# DM6010.net
KiCad netlist of a schematic drawn in Altium Designer
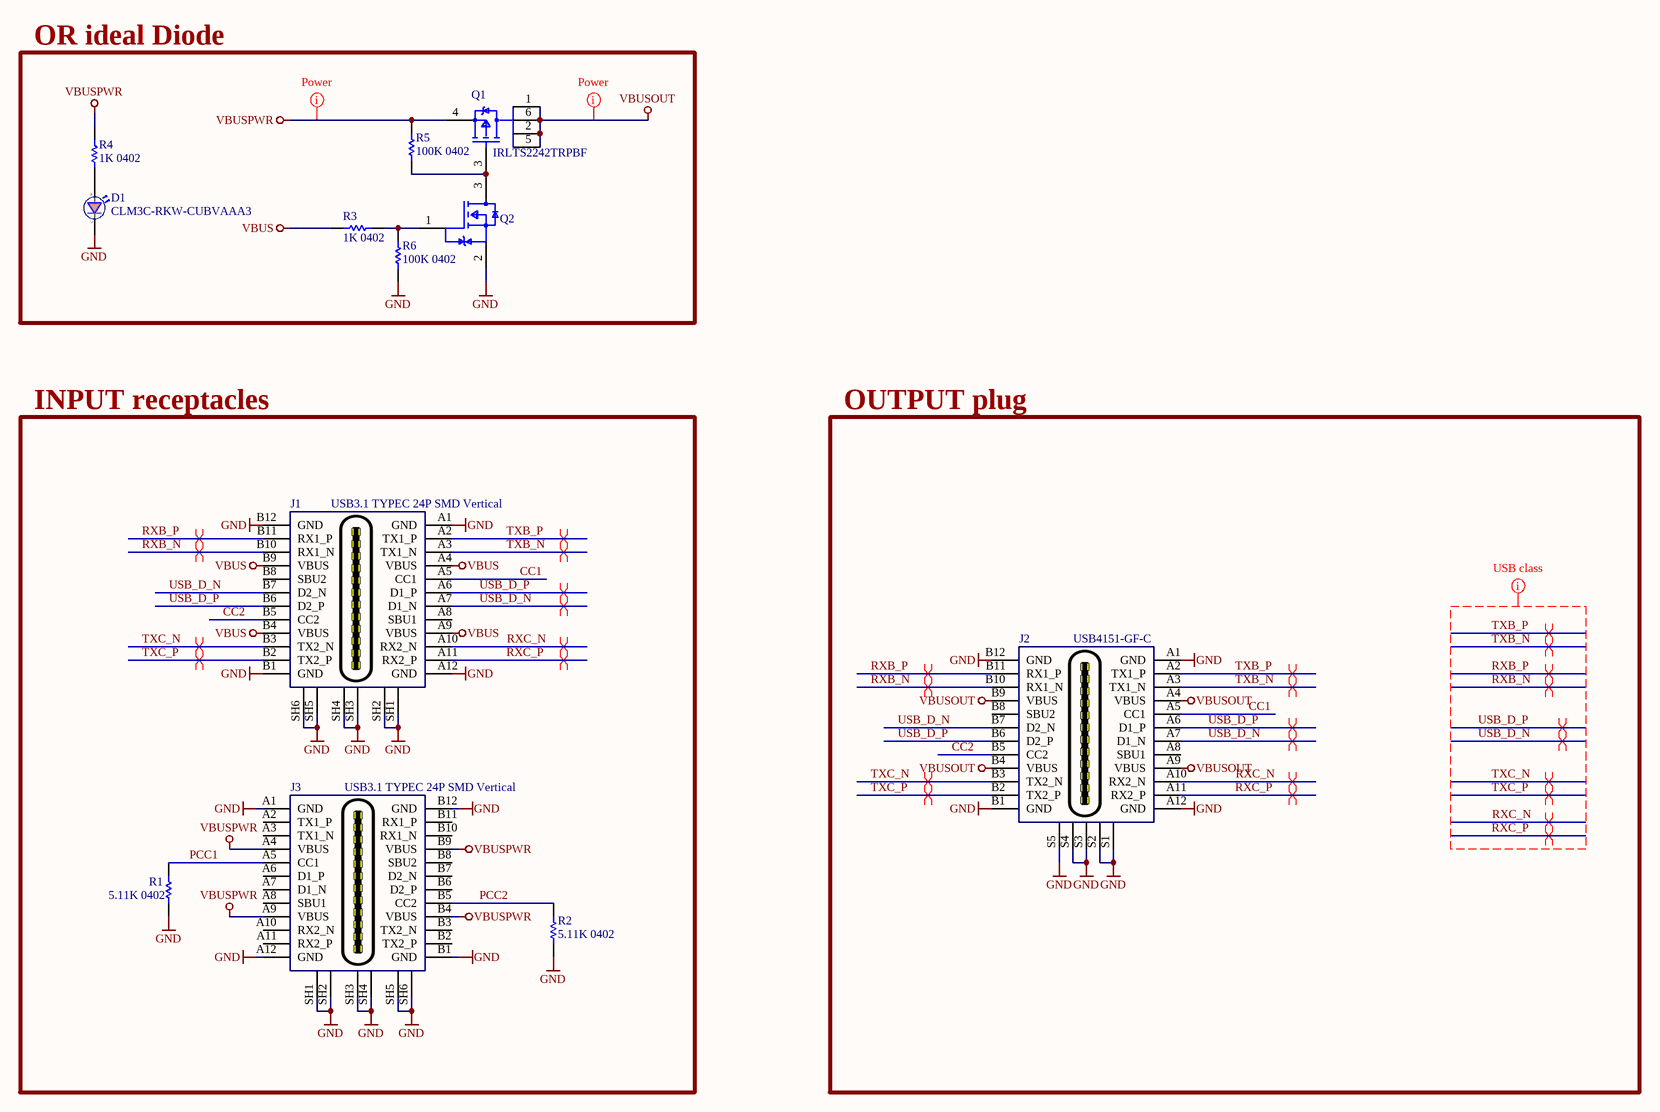
[diagram p0: DM6010.SchDoc]

(export (version "E")
  (design (tool "Eeschema 10.0.6"))
  (components
    (comp (ref "D1")
      (value "CLM3C-RKW-CUBVAAA3")
      (footprint "CLM3C-RKW-CUBVAAA3")
      (description "Single Color LED, Red")
      (libsource (lib "DM6010_R0M0E0") (part "CLM3C-RKW-CUBVAAA3"))
    )
    (comp (ref "J1")
      (value "USB3.1 TYPEC 24P SMD Vertical")
      (footprint "DM6010_R0M0E0:CX80B1-24P")
      (description "CONN RCPT USB3.1 TYPEC 24POS SMD Vertical")
      (libsource (lib "") (part "CX80B1-24P_1"))
    )
    (comp (ref "J2")
      (value "USB4151-GF-C")
      (footprint "GCT_USB4151-GF-C_REVA")
      (description "USB Connector, 24 Contact(s), Male, Straight, Surface Mount Terminal, Locking, Plug")
      (libsource (lib "DM6010_R0M0E0") (part "USB4151-GF-C"))
    )
    (comp (ref "J3")
      (value "USB3.1 TYPEC 24P SMD Vertical")
      (footprint "DM6010_R0M0E0:CX80B1-24P")
      (description "CONN RCPT USB3.1 TYPEC 24POS SMD Vertical")
      (libsource (lib "DM6010_R0M0E0") (part "CX80B1-24P"))
    )
    (comp (ref "Q1")
      (value "IRLTS2242TRPBF")
      (footprint "TSOP-6-MFG")
      (description "MOSFET P-CH 20V 6.9A 6TSOP")
      (libsource (lib "DM6010_R0M0E0") (part "IRLTS2242TRPBF"))
    )
    (comp (ref "Q2")
      (value "RE1C002UNTCL")
      (footprint "LuxonisMaster:RE1C002UNTCL")
      (description "VISHAY - SI1062X-T1-GE3 - MOSFET Transistor, N Channel, 530 mA, 20 V, 0.35 ohm, 4.5 V, 1 V")
      (libsource (lib "LuxonisMaster") (part "RE1C002UNTCL"))
    )
    (comp (ref "R1")
      (value "5.11K 0402")
      (footprint "RES_Altium_Vault_Generic:RESC0402(1005)_L")
      (fields (field (name "TOLERANCE") "1%"))
      (libsource (lib "LuxonisMaster") (part "RC0402FR-075K11L"))
    )
    (comp (ref "R2")
      (value "5.11K 0402")
      (footprint "RES_Altium_Vault_Generic:RESC0402(1005)_L")
      (fields (field (name "TOLERANCE") "1%"))
      (libsource (lib "LuxonisMaster") (part "RC0402FR-075K11L"))
    )
    (comp (ref "R3")
      (value "1K 0402")
      (footprint "RES_Altium_Vault_Generic:RESC0402(1005)_L")
      (fields (field (name "TOLERANCE") "1%"))
      (libsource (lib "LuxonisMaster") (part "RC0402FR-071KL"))
    )
    (comp (ref "R4")
      (value "1K 0402")
      (footprint "RES_Altium_Vault_Generic:RESC0402(1005)_L")
      (fields (field (name "TOLERANCE") "1%"))
      (libsource (lib "LuxonisMaster") (part "RC0402FR-071KL"))
    )
    (comp (ref "R5")
      (value "100K 0402")
      (footprint "RES_Altium_Vault_Generic:RESC0402(1005)_L")
      (description "RES SMD 100K OHM 1% 1/16W 0402")
      (fields (field (name "TOLERANCE") "1%"))
      (libsource (lib "LuxonisMaster") (part "RC0402FR-07100KL"))
    )
    (comp (ref "R6")
      (value "100K 0402")
      (footprint "RES_Altium_Vault_Generic:RESC0402(1005)_L")
      (description "RES SMD 100K OHM 1% 1/16W 0402")
      (fields (field (name "TOLERANCE") "1%"))
      (libsource (lib "LuxonisMaster") (part "RC0402FR-07100KL"))
    )
  )
  (nets
    (net (code "1") (name "/CC1") (class "Default")
      (node (ref "J1") (pin "A5") (pinfunction "CC1_A5") (pintype "passive"))
      (node (ref "J2") (pin "A5") (pinfunction "CC1_A5") (pintype "passive"))
    )
    (net (code "2") (name "/CC2") (class "Default")
      (node (ref "J1") (pin "B5") (pinfunction "CC2_B5") (pintype "passive"))
      (node (ref "J2") (pin "B5") (pinfunction "CC2_B5") (pintype "passive"))
    )
    (net (code "3") (name "/PCC1") (class "Default")
      (node (ref "J3") (pin "A5") (pinfunction "CC1_A5") (pintype "passive"))
      (node (ref "R1") (pin "2") (pinfunction "2_2") (pintype "passive"))
    )
    (net (code "4") (name "/PCC2") (class "Default")
      (node (ref "J3") (pin "B5") (pinfunction "CC2_B5") (pintype "passive"))
      (node (ref "R2") (pin "2") (pinfunction "2_2") (pintype "passive"))
    )
    (net (code "5") (name "/RXB_N") (class "Default")
      (node (ref "J1") (pin "B10") (pinfunction "RX1_N_B10") (pintype "passive"))
      (node (ref "J2") (pin "B10") (pinfunction "RX1_N_B10") (pintype "passive"))
    )
    (net (code "6") (name "/RXB_P") (class "Default")
      (node (ref "J1") (pin "B11") (pinfunction "RX1_P_B11") (pintype "passive"))
      (node (ref "J2") (pin "B11") (pinfunction "RX1_P_B11") (pintype "passive"))
    )
    (net (code "7") (name "/RXC_N") (class "Default")
      (node (ref "J1") (pin "A10") (pinfunction "RX2_N_A10") (pintype "passive"))
      (node (ref "J2") (pin "A10") (pinfunction "RX2_N_A10") (pintype "passive"))
    )
    (net (code "8") (name "/RXC_P") (class "Default")
      (node (ref "J1") (pin "A11") (pinfunction "RX2_P_A11") (pintype "passive"))
      (node (ref "J2") (pin "A11") (pinfunction "RX2_P_A11") (pintype "passive"))
    )
    (net (code "9") (name "/TXB_N") (class "Default")
      (node (ref "J1") (pin "A3") (pinfunction "TX1_N_A3") (pintype "passive"))
      (node (ref "J2") (pin "A3") (pinfunction "TX1_N_A3") (pintype "passive"))
    )
    (net (code "10") (name "/TXB_P") (class "Default")
      (node (ref "J1") (pin "A2") (pinfunction "TX1_P_A2") (pintype "passive"))
      (node (ref "J2") (pin "A2") (pinfunction "TX1_P_A2") (pintype "passive"))
    )
    (net (code "11") (name "/TXC_N") (class "Default")
      (node (ref "J1") (pin "B3") (pinfunction "TX2_N_B3") (pintype "passive"))
      (node (ref "J2") (pin "B3") (pinfunction "TX2_N_B3") (pintype "passive"))
    )
    (net (code "12") (name "/TXC_P") (class "Default")
      (node (ref "J1") (pin "B2") (pinfunction "TX2_P_B2") (pintype "passive"))
      (node (ref "J2") (pin "B2") (pinfunction "TX2_P_B2") (pintype "passive"))
    )
    (net (code "13") (name "/USB_D_N") (class "Default")
      (node (ref "J1") (pin "A7") (pinfunction "D1_N_A7") (pintype "passive"))
      (node (ref "J1") (pin "B7") (pinfunction "D2_N_B7") (pintype "passive"))
      (node (ref "J2") (pin "A7") (pinfunction "D1_N_A7") (pintype "passive"))
      (node (ref "J2") (pin "B7") (pinfunction "D2_N_B7") (pintype "passive"))
    )
    (net (code "14") (name "/USB_D_P") (class "Default")
      (node (ref "J1") (pin "A6") (pinfunction "D1_P_A6") (pintype "passive"))
      (node (ref "J1") (pin "B6") (pinfunction "D2_P_B6") (pintype "passive"))
      (node (ref "J2") (pin "A6") (pinfunction "D1_P_A6") (pintype "passive"))
      (node (ref "J2") (pin "B6") (pinfunction "D2_P_B6") (pintype "passive"))
    )
    (net (code "15") (name "GND") (class "Default")
      (node (ref "D1") (pin "2") (pinfunction "C_2") (pintype "passive"))
      (node (ref "J1") (pin "A1") (pinfunction "GND_A1") (pintype "passive"))
      (node (ref "J1") (pin "A12") (pinfunction "GND_A12") (pintype "passive"))
      (node (ref "J1") (pin "B1") (pinfunction "GND_B1") (pintype "passive"))
      (node (ref "J1") (pin "B12") (pinfunction "GND_B12") (pintype "passive"))
      (node (ref "J1") (pin "SH1") (pinfunction "SH_SH1") (pintype "passive"))
      (node (ref "J1") (pin "SH2") (pinfunction "SH_SH2") (pintype "passive"))
      (node (ref "J1") (pin "SH3") (pinfunction "SH_SH3") (pintype "passive"))
      (node (ref "J1") (pin "SH4") (pinfunction "SH_SH4") (pintype "passive"))
      (node (ref "J1") (pin "SH5") (pinfunction "SH_SH5") (pintype "passive"))
      (node (ref "J1") (pin "SH6") (pinfunction "SH_SH6") (pintype "passive"))
      (node (ref "J2") (pin "A1") (pinfunction "GND_A1") (pintype "passive"))
      (node (ref "J2") (pin "A12") (pinfunction "GND_A12") (pintype "passive"))
      (node (ref "J2") (pin "B1") (pinfunction "GND_B1") (pintype "passive"))
      (node (ref "J2") (pin "B12") (pinfunction "GND_B12") (pintype "passive"))
      (node (ref "J2") (pin "S1") (pinfunction "SH_S1") (pintype "passive"))
      (node (ref "J2") (pin "S2") (pinfunction "SH_S2") (pintype "passive"))
      (node (ref "J2") (pin "S3") (pinfunction "SH_S3") (pintype "passive"))
      (node (ref "J2") (pin "S4") (pinfunction "SH_S4") (pintype "passive"))
      (node (ref "J2") (pin "S5") (pinfunction "SH_S5") (pintype "passive"))
      (node (ref "J3") (pin "A1") (pinfunction "GND_A1") (pintype "passive"))
      (node (ref "J3") (pin "A12") (pinfunction "GND_A12") (pintype "passive"))
      (node (ref "J3") (pin "B1") (pinfunction "GND_B1") (pintype "passive"))
      (node (ref "J3") (pin "B12") (pinfunction "GND_B12") (pintype "passive"))
      (node (ref "J3") (pin "SH1") (pinfunction "SH_SH1") (pintype "passive"))
      (node (ref "J3") (pin "SH2") (pinfunction "SH_SH2") (pintype "passive"))
      (node (ref "J3") (pin "SH3") (pinfunction "SH_SH3") (pintype "passive"))
      (node (ref "J3") (pin "SH4") (pinfunction "SH_SH4") (pintype "passive"))
      (node (ref "J3") (pin "SH5") (pinfunction "SH_SH5") (pintype "passive"))
      (node (ref "J3") (pin "SH6") (pinfunction "SH_SH6") (pintype "passive"))
      (node (ref "Q2") (pin "2") (pinfunction "Source_2") (pintype "passive"))
      (node (ref "R1") (pin "1") (pinfunction "1_1") (pintype "passive"))
      (node (ref "R2") (pin "1") (pinfunction "1_1") (pintype "passive"))
      (node (ref "R6") (pin "1") (pinfunction "1_1") (pintype "passive"))
    )
    (net (code "16") (name "Net-(D1-A)") (class "Default")
      (node (ref "D1") (pin "1") (pinfunction "A_1") (pintype "passive"))
      (node (ref "R4") (pin "1") (pinfunction "1_1") (pintype "passive"))
    )
    (net (code "17") (name "Net-(Q1-G)") (class "Default")
      (node (ref "Q1") (pin "3") (pinfunction "G_3") (pintype "passive"))
      (node (ref "Q2") (pin "3") (pinfunction "Drain_3") (pintype "passive"))
      (node (ref "R5") (pin "1") (pinfunction "1_1") (pintype "passive"))
    )
    (net (code "18") (name "Net-(Q2-Gate)") (class "Default")
      (node (ref "Q2") (pin "1") (pinfunction "Gate_1") (pintype "passive"))
      (node (ref "R3") (pin "2") (pinfunction "2_2") (pintype "passive"))
      (node (ref "R6") (pin "2") (pinfunction "2_2") (pintype "passive"))
    )
    (net (code "19") (name "VBUS") (class "Default")
      (node (ref "J1") (pin "A4") (pinfunction "VBUS_A4") (pintype "passive"))
      (node (ref "J1") (pin "A9") (pinfunction "VBUS_A9") (pintype "passive"))
      (node (ref "J1") (pin "B4") (pinfunction "VBUS_B4") (pintype "passive"))
      (node (ref "J1") (pin "B9") (pinfunction "VBUS_B9") (pintype "passive"))
      (node (ref "R3") (pin "1") (pinfunction "1_1") (pintype "passive"))
    )
    (net (code "20") (name "VBUSOUT") (class "Default")
      (node (ref "J2") (pin "A4") (pinfunction "VBUS_A4") (pintype "passive"))
      (node (ref "J2") (pin "A9") (pinfunction "VBUS_A9") (pintype "passive"))
      (node (ref "J2") (pin "B4") (pinfunction "VBUS_B4") (pintype "passive"))
      (node (ref "J2") (pin "B9") (pinfunction "VBUS_B9") (pintype "passive"))
      (node (ref "Q1") (pin "1") (pinfunction "D_1") (pintype "passive"))
      (node (ref "Q1") (pin "2") (pinfunction "D_2") (pintype "passive"))
      (node (ref "Q1") (pin "5") (pinfunction "D_5") (pintype "passive"))
      (node (ref "Q1") (pin "6") (pinfunction "D_6") (pintype "passive"))
    )
    (net (code "21") (name "VBUSPWR") (class "Default")
      (node (ref "J3") (pin "A4") (pinfunction "VBUS_A4") (pintype "passive"))
      (node (ref "J3") (pin "A9") (pinfunction "VBUS_A9") (pintype "passive"))
      (node (ref "J3") (pin "B4") (pinfunction "VBUS_B4") (pintype "passive"))
      (node (ref "J3") (pin "B9") (pinfunction "VBUS_B9") (pintype "passive"))
      (node (ref "Q1") (pin "4") (pinfunction "S_4") (pintype "passive"))
      (node (ref "R4") (pin "2") (pinfunction "2_2") (pintype "passive"))
      (node (ref "R5") (pin "2") (pinfunction "2_2") (pintype "passive"))
    )
    (net (code "22") (name "unconnected-(J1-SBU1-PadA8)") (class "Default")
      (node (ref "J1") (pin "A8") (pinfunction "SBU1_A8") (pintype "passive"))
    )
    (net (code "23") (name "unconnected-(J1-SBU2-PadB8)") (class "Default")
      (node (ref "J1") (pin "B8") (pinfunction "SBU2_B8") (pintype "passive"))
    )
    (net (code "24") (name "unconnected-(J2-SBU1-PadA8)") (class "Default")
      (node (ref "J2") (pin "A8") (pinfunction "SBU1_A8") (pintype "passive"))
    )
    (net (code "25") (name "unconnected-(J2-SBU2-PadB8)") (class "Default")
      (node (ref "J2") (pin "B8") (pinfunction "SBU2_B8") (pintype "passive"))
    )
    (net (code "26") (name "unconnected-(J3-D1_N-PadA7)") (class "Default")
      (node (ref "J3") (pin "A7") (pinfunction "D1_N_A7") (pintype "passive"))
    )
    (net (code "27") (name "unconnected-(J3-D1_P-PadA6)") (class "Default")
      (node (ref "J3") (pin "A6") (pinfunction "D1_P_A6") (pintype "passive"))
    )
    (net (code "28") (name "unconnected-(J3-D2_N-PadB7)") (class "Default")
      (node (ref "J3") (pin "B7") (pinfunction "D2_N_B7") (pintype "passive"))
    )
    (net (code "29") (name "unconnected-(J3-D2_P-PadB6)") (class "Default")
      (node (ref "J3") (pin "B6") (pinfunction "D2_P_B6") (pintype "passive"))
    )
    (net (code "30") (name "unconnected-(J3-RX1_N-PadB10)") (class "Default")
      (node (ref "J3") (pin "B10") (pinfunction "RX1_N_B10") (pintype "passive"))
    )
    (net (code "31") (name "unconnected-(J3-RX1_P-PadB11)") (class "Default")
      (node (ref "J3") (pin "B11") (pinfunction "RX1_P_B11") (pintype "passive"))
    )
    (net (code "32") (name "unconnected-(J3-RX2_N-PadA10)") (class "Default")
      (node (ref "J3") (pin "A10") (pinfunction "RX2_N_A10") (pintype "passive"))
    )
    (net (code "33") (name "unconnected-(J3-RX2_P-PadA11)") (class "Default")
      (node (ref "J3") (pin "A11") (pinfunction "RX2_P_A11") (pintype "passive"))
    )
    (net (code "34") (name "unconnected-(J3-SBU1-PadA8)") (class "Default")
      (node (ref "J3") (pin "A8") (pinfunction "SBU1_A8") (pintype "passive"))
    )
    (net (code "35") (name "unconnected-(J3-SBU2-PadB8)") (class "Default")
      (node (ref "J3") (pin "B8") (pinfunction "SBU2_B8") (pintype "passive"))
    )
    (net (code "36") (name "unconnected-(J3-TX1_N-PadA3)") (class "Default")
      (node (ref "J3") (pin "A3") (pinfunction "TX1_N_A3") (pintype "passive"))
    )
    (net (code "37") (name "unconnected-(J3-TX1_P-PadA2)") (class "Default")
      (node (ref "J3") (pin "A2") (pinfunction "TX1_P_A2") (pintype "passive"))
    )
    (net (code "38") (name "unconnected-(J3-TX2_N-PadB3)") (class "Default")
      (node (ref "J3") (pin "B3") (pinfunction "TX2_N_B3") (pintype "passive"))
    )
    (net (code "39") (name "unconnected-(J3-TX2_P-PadB2)") (class "Default")
      (node (ref "J3") (pin "B2") (pinfunction "TX2_P_B2") (pintype "passive"))
    )
  )
)
